# Blink_Blink_Beep_Boop.net
KiCad netlist of a schematic drawn in Altium Designer
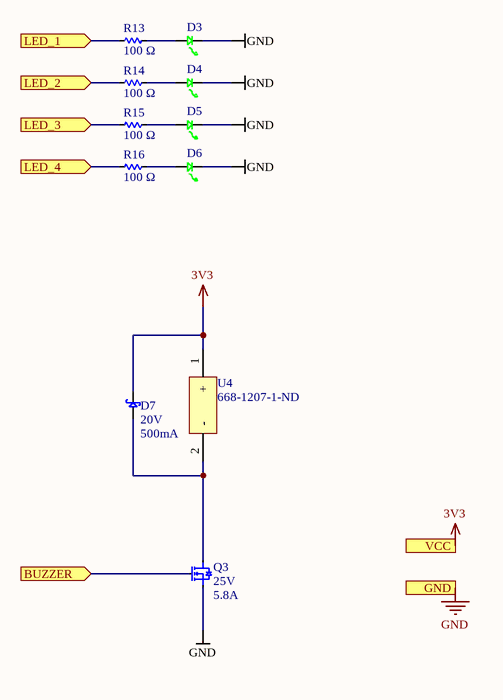
[diagram p0: Blink_Blink_Beep_Boop.SchDoc]

(export (version "E")
  (design (tool "Eeschema 10.0.6"))
  (components
    (comp (ref "D3")
      (value "LED_LY971")
      (footprint "0805_Diode")
      (description "LED 0805 GREEN 20MA")
      (fields
        (field (name "MANUFACTURER") "OSRAM Opto Semiconductors Inc")
        (field (name "MANUFACTURER PART NUMBER") "LG R971-KN-1")
      )
      (libsource (lib "SSI") (part "LED_LY971"))
    )
    (comp (ref "D4")
      (value "LED_LY971")
      (footprint "0805_Diode")
      (description "LED 0805 GREEN 20MA")
      (fields
        (field (name "MANUFACTURER") "OSRAM Opto Semiconductors Inc")
        (field (name "MANUFACTURER PART NUMBER") "LG R971-KN-1")
      )
      (libsource (lib "SSI") (part "LED_LY971"))
    )
    (comp (ref "D5")
      (value "LED_LY971")
      (footprint "0805_Diode")
      (description "LED 0805 GREEN 20MA")
      (fields
        (field (name "MANUFACTURER") "OSRAM Opto Semiconductors Inc")
        (field (name "MANUFACTURER PART NUMBER") "LG R971-KN-1")
      )
      (libsource (lib "SSI") (part "LED_LY971"))
    )
    (comp (ref "D6")
      (value "LED_LY971")
      (footprint "0805_Diode")
      (description "LED 0805 GREEN 20MA")
      (fields
        (field (name "MANUFACTURER") "OSRAM Opto Semiconductors Inc")
        (field (name "MANUFACTURER PART NUMBER") "LG R971-KN-1")
      )
      (libsource (lib "SSI") (part "LED_LY971"))
    )
    (comp (ref "D7")
      (value "SCHOTTKY_MBR0520L")
      (footprint "SOD123")
      (description "DIODE SCHOTTKY 0.5A 20V SOD-123")
      (fields
        (field (name "MANUFACTURER") "Fairchild Semiconductor")
        (field (name "MANUFACTURER PART NUMBER") "MBR0520L")
        (field (name "VOLTAGE - DC REVERSE (VR) (MAX)") "20V")
        (field (name "CURRENT - AVERAGE RECTIFIED (IO)") "500mA")
      )
      (libsource (lib "SSI") (part "SCHOTTKY_MBR0520L"))
    )
    (comp (ref "Q3")
      (value "MOSFET N-CH 60V 1.7A SSOT3")
      (footprint "3SOT23")
      (description "MOSFET N-CH 25V 5.8A SOT23")
      (fields
        (field (name "MANUFACTURER") "International Rectifier")
        (field (name "MANUFACTURER PART NUMBER") "IRFML8244TRPBF")
        (field (name "DRAIN TO SOURCE VOLTAGE (VDSS)") "25V")
        (field (name "CURRENT - CONTINUOUS DRAIN (ID) @ 25° C") "5.8A")
      )
      (libsource (lib "SSI") (part "NFET_IRFML8244TRPBF"))
    )
    (comp (ref "R13")
      (value "__template_resistor")
      (footprint "R0603")
      (description "RES SMD 100 OHM 1% 1/10W 0603")
      (fields
        (field (name "MANUFACTURER PART NUMBER") "RC0603FR-07100RL")
        (field (name "MANUFACTURER") "Yageo")
        (field (name "RESISTANCE") "100 Ω")
      )
      (libsource (lib "passives") (part "__template_resistor"))
    )
    (comp (ref "R14")
      (value "__template_resistor")
      (footprint "R0603")
      (description "RES SMD 100 OHM 1% 1/10W 0603")
      (fields
        (field (name "MANUFACTURER PART NUMBER") "RC0603FR-07100RL")
        (field (name "MANUFACTURER") "Yageo")
        (field (name "RESISTANCE") "100 Ω")
      )
      (libsource (lib "passives") (part "__template_resistor"))
    )
    (comp (ref "R15")
      (value "__template_resistor")
      (footprint "R0603")
      (description "RES SMD 100 OHM 1% 1/10W 0603")
      (fields
        (field (name "MANUFACTURER PART NUMBER") "RC0603FR-07100RL")
        (field (name "MANUFACTURER") "Yageo")
        (field (name "RESISTANCE") "100 Ω")
      )
      (libsource (lib "passives") (part "__template_resistor"))
    )
    (comp (ref "R16")
      (value "__template_resistor")
      (footprint "R0603")
      (description "RES SMD 100 OHM 1% 1/10W 0603")
      (fields
        (field (name "MANUFACTURER PART NUMBER") "RC0603FR-07100RL")
        (field (name "MANUFACTURER") "Yageo")
        (field (name "RESISTANCE") "100 Ω")
      )
      (libsource (lib "passives") (part "__template_resistor"))
    )
    (comp (ref "U4")
      (value "BUZ_SMT-0540-T-7-R")
      (footprint "BUZ_SMT-0540-T-7-R")
      (description "Peak-Peak Signal Buzzer Single Tone 4kHz Magnetic 2 ~ 4V 78dB @ 3V, 10cm")
      (fields
        (field (name "MANUFACTURER") "PUI Audio, Inc.")
        (field (name "MANUFACTURER PART NUMBER") "SMT-0540-T-7-R")
        (field (name "SUPPLIER PART NUMBER 1") "668-1207-1-ND")
      )
      (libsource (lib "SSI") (part "BUZ_SMT-0540-T-7-R"))
    )
  )
  (nets
    (net (code "1") (name "/BUZZER") (class "Default") (node (ref "Q3") (pin "1") (pintype "passive")))
    (net (code "2") (name "/LED_1") (class "Default") (node (ref "R13") (pin "1") (pintype "passive")))
    (net (code "3") (name "/LED_2") (class "Default") (node (ref "R14") (pin "1") (pintype "passive")))
    (net (code "4") (name "/LED_3") (class "Default") (node (ref "R15") (pin "1") (pintype "passive")))
    (net (code "5") (name "/LED_4") (class "Default") (node (ref "R16") (pin "1") (pintype "passive")))
    (net (code "6") (name "3V3") (class "Default")
      (node (ref "D7") (pin "2") (pintype "passive"))
      (node (ref "U4") (pin "1") (pinfunction "+_1") (pintype "passive"))
    )
    (net (code "7") (name "GND") (class "Default")
      (node (ref "D3") (pin "1") (pintype "passive"))
      (node (ref "D4") (pin "1") (pintype "passive"))
      (node (ref "D5") (pin "1") (pintype "passive"))
      (node (ref "D6") (pin "1") (pintype "passive"))
      (node (ref "Q3") (pin "2") (pintype "passive"))
    )
    (net (code "8") (name "Net-(D3-Pad2)") (class "Default")
      (node (ref "D3") (pin "2") (pintype "passive"))
      (node (ref "R13") (pin "2") (pintype "passive"))
    )
    (net (code "9") (name "Net-(D4-Pad2)") (class "Default")
      (node (ref "D4") (pin "2") (pintype "passive"))
      (node (ref "R14") (pin "2") (pintype "passive"))
    )
    (net (code "10") (name "Net-(D5-Pad2)") (class "Default")
      (node (ref "D5") (pin "2") (pintype "passive"))
      (node (ref "R15") (pin "2") (pintype "passive"))
    )
    (net (code "11") (name "Net-(D6-Pad2)") (class "Default")
      (node (ref "D6") (pin "2") (pintype "passive"))
      (node (ref "R16") (pin "2") (pintype "passive"))
    )
    (net (code "12") (name "Net-(U4--)") (class "Default")
      (node (ref "D7") (pin "1") (pintype "passive"))
      (node (ref "Q3") (pin "3") (pintype "passive"))
      (node (ref "U4") (pin "2") (pinfunction "-_2") (pintype "passive"))
    )
  )
)
